# Tunable_Capacitance.net
KiCad netlist of a schematic drawn in Altium Designer
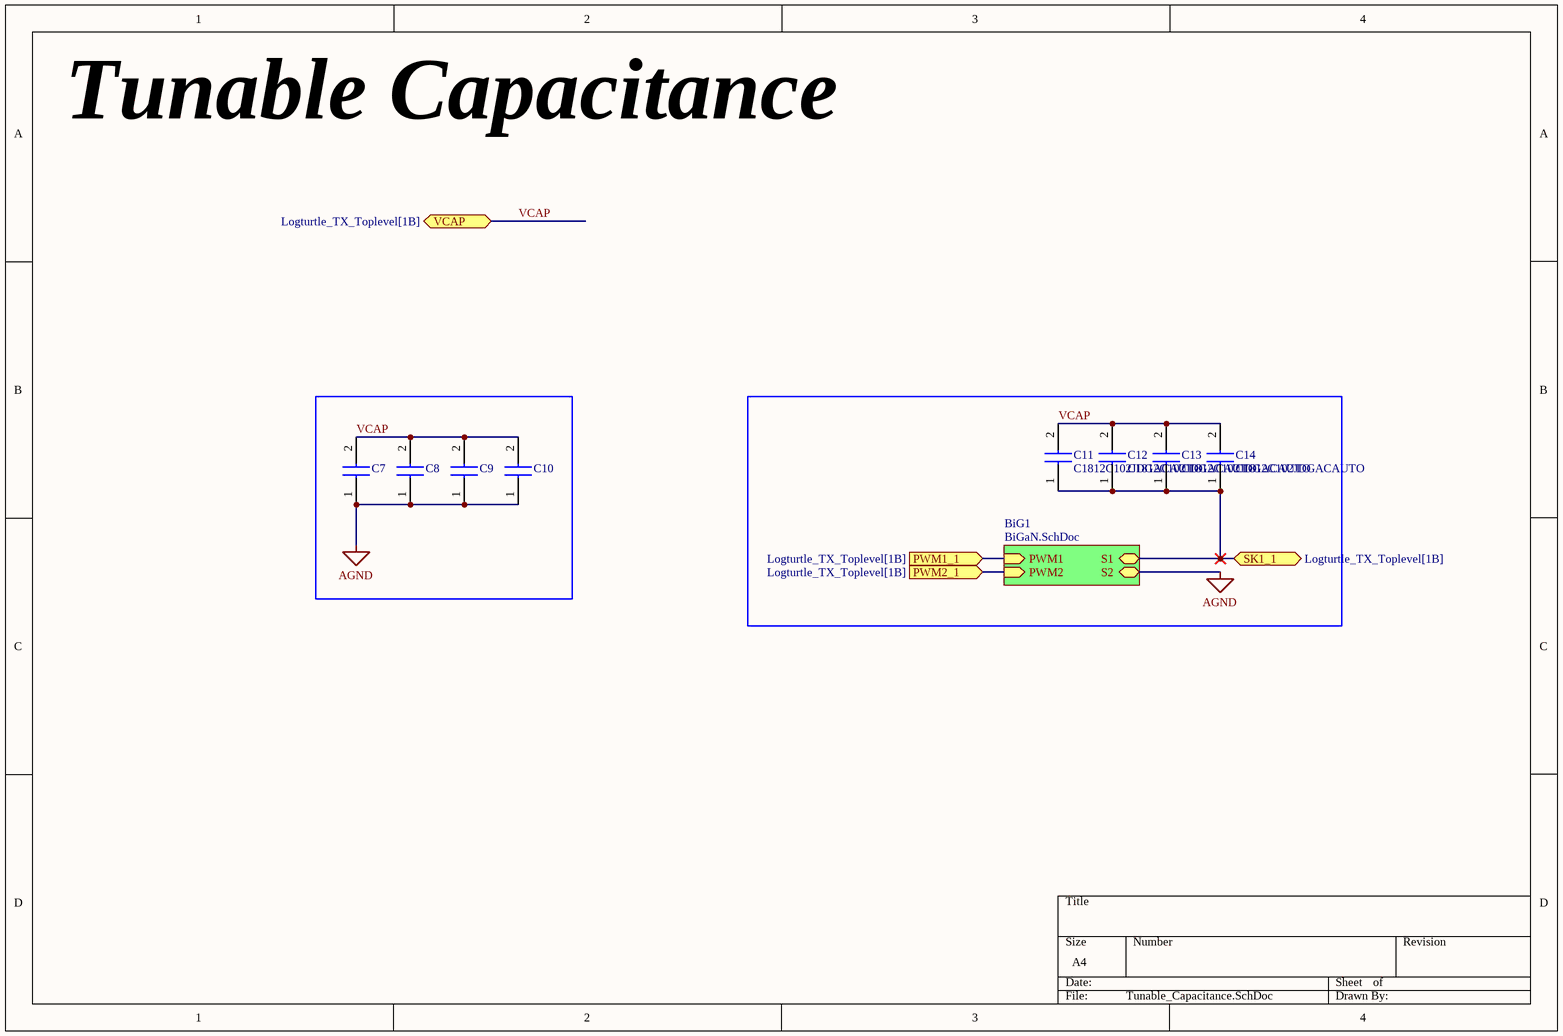
[diagram p0: Tunable_Capacitance.SchDoc]

(export (version "E")
  (design (tool "Eeschema 10.0.6"))
  (components
    (comp (ref "C7")
      (value "C1812C102JDGACAUTO")
      (footprint "C1812")
      (description "Capacitor")
      (libsource (lib "LOGTURTLE_APR_25_TX") (part "C1812C102JDGACAUTO"))
    )
    (comp (ref "C8")
      (value "C1812C102JDGACAUTO")
      (footprint "C1812")
      (description "Capacitor")
      (libsource (lib "LOGTURTLE_APR_25_TX") (part "C1812C102JDGACAUTO"))
    )
    (comp (ref "C9")
      (value "C1812C102JDGACAUTO")
      (footprint "C1812")
      (description "Capacitor")
      (libsource (lib "LOGTURTLE_APR_25_TX") (part "C1812C102JDGACAUTO"))
    )
    (comp (ref "C10")
      (value "C1812C102JDGACAUTO")
      (footprint "C1812")
      (description "Capacitor")
      (libsource (lib "LOGTURTLE_APR_25_TX") (part "C1812C102JDGACAUTO"))
    )
    (comp (ref "C11")
      (value "C1812C102JDGACAUTO")
      (footprint "C1812")
      (description "Capacitor")
      (libsource (lib "LOGTURTLE_APR_25_TX") (part "C1812C102JDGACAUTO"))
    )
    (comp (ref "C12")
      (value "C1812C102JDGACAUTO")
      (footprint "C1812")
      (description "Capacitor")
      (libsource (lib "LOGTURTLE_APR_25_TX") (part "C1812C102JDGACAUTO"))
    )
    (comp (ref "C13")
      (value "C1812C102JDGACAUTO")
      (footprint "C1812")
      (description "Capacitor")
      (libsource (lib "LOGTURTLE_APR_25_TX") (part "C1812C102JDGACAUTO"))
    )
    (comp (ref "C14")
      (value "C1812C102JDGACAUTO")
      (footprint "C1812")
      (description "Capacitor")
      (libsource (lib "LOGTURTLE_APR_25_TX") (part "C1812C102JDGACAUTO"))
    )
  )
  (nets
    (net (code "3") (name "/SK1_1") (class "Default")
      (node (ref "C11") (pin "1") (pinfunction "1_1") (pintype "passive"))
      (node (ref "C12") (pin "1") (pinfunction "1_1") (pintype "passive"))
      (node (ref "C13") (pin "1") (pinfunction "1_1") (pintype "passive"))
      (node (ref "C14") (pin "1") (pinfunction "1_1") (pintype "passive"))
    )
    (net (code "4") (name "/VCAP") (class "Default")
      (node (ref "C10") (pin "2") (pinfunction "2_2") (pintype "passive"))
      (node (ref "C11") (pin "2") (pinfunction "2_2") (pintype "passive"))
      (node (ref "C12") (pin "2") (pinfunction "2_2") (pintype "passive"))
      (node (ref "C13") (pin "2") (pinfunction "2_2") (pintype "passive"))
      (node (ref "C14") (pin "2") (pinfunction "2_2") (pintype "passive"))
      (node (ref "C7") (pin "2") (pinfunction "2_2") (pintype "passive"))
      (node (ref "C8") (pin "2") (pinfunction "2_2") (pintype "passive"))
      (node (ref "C9") (pin "2") (pinfunction "2_2") (pintype "passive"))
    )
    (net (code "5") (name "AGND") (class "Default")
      (node (ref "C10") (pin "1") (pinfunction "1_1") (pintype "passive"))
      (node (ref "C7") (pin "1") (pinfunction "1_1") (pintype "passive"))
      (node (ref "C8") (pin "1") (pinfunction "1_1") (pintype "passive"))
      (node (ref "C9") (pin "1") (pinfunction "1_1") (pintype "passive"))
    )
  )
)
